# gps.net
KiCad netlist of a schematic drawn in EAGLE
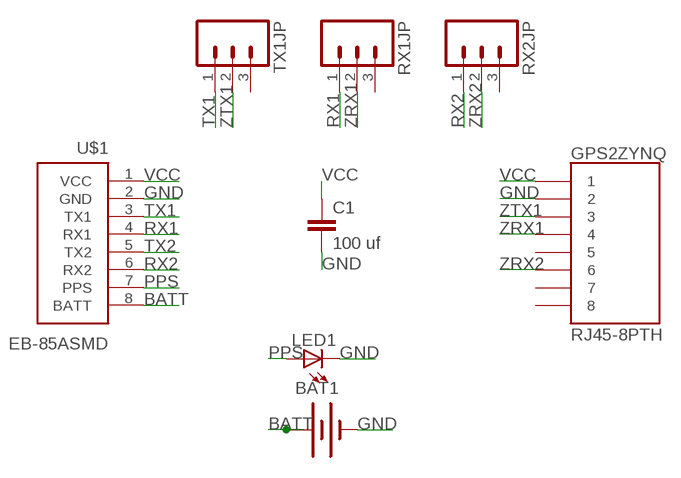
[diagram p0: schematic, sheet 1]

(export (version "E")
  (design (tool "Eeschema 10.0.6"))
  (components
    (comp (ref "BAT1")
      (value "BATTERY12PTH")
      (footprint "eagle-import:BATTCON_12MM_PTH")
      (libsource (lib "eagle-import") (part "BATTERY12PTH"))
    )
    (comp (ref "C1")
      (value "100 uf")
      (footprint "eagle-import:CAP-PTH-5MM")
      (libsource (lib "eagle-import") (part "CAPPTH1"))
    )
    (comp (ref "GPS2ZYNQ")
      (value "RJ45-8PTH")
      (footprint "eagle-import:RJ45-8")
      (libsource (lib "eagle-import") (part "RJ45-8PTH"))
    )
    (comp (ref "LED1")
      (value "LED5MM")
      (footprint "eagle-import:LED5MM")
      (libsource (lib "eagle-import") (part "LED5MM"))
    )
    (comp (ref "RX1JP")
      (value "M03LONGPADS")
      (footprint "eagle-import:1X03_LONGPADS")
      (libsource (lib "eagle-import") (part "M03LONGPADS"))
    )
    (comp (ref "RX2JP")
      (value "M03LONGPADS")
      (footprint "eagle-import:1X03_LONGPADS")
      (libsource (lib "eagle-import") (part "M03LONGPADS"))
    )
    (comp (ref "TX1JP")
      (value "M03LONGPADS")
      (footprint "eagle-import:1X03_LONGPADS")
      (libsource (lib "eagle-import") (part "M03LONGPADS"))
    )
    (comp (ref "U$1")
      (value "EB-85ASMD")
      (footprint "eagle-import:EB-85A")
      (libsource (lib "eagle-import") (part "EB-85ASMD"))
    )
  )
  (nets
    (net (code "1") (name "/BATT") (class "Default")
      (node (ref "BAT1") (pin "VCC@1") (pinfunction "+_VCC@1") (pintype "power_in"))
      (node (ref "U$1") (pin "8") (pinfunction "BATT_8") (pintype "power_in"))
    )
    (net (code "2") (name "/GND") (class "Default")
      (node (ref "BAT1") (pin "GND") (pinfunction "-_GND") (pintype "power_in"))
      (node (ref "C1") (pin "2") (pinfunction "2_2") (pintype "passive"))
      (node (ref "GPS2ZYNQ") (pin "2") (pinfunction "2_2") (pintype "bidirectional"))
      (node (ref "LED1") (pin "K") (pinfunction "C_K") (pintype "passive"))
      (node (ref "U$1") (pin "2") (pinfunction "GND_2") (pintype "power_in"))
    )
    (net (code "3") (name "/PPS") (class "Default")
      (node (ref "LED1") (pin "A") (pinfunction "A_A") (pintype "passive"))
      (node (ref "U$1") (pin "7") (pinfunction "PPS_7") (pintype "output"))
    )
    (net (code "4") (name "/RX1") (class "Default")
      (node (ref "RX1JP") (pin "1") (pinfunction "1_1") (pintype "passive"))
      (node (ref "U$1") (pin "4") (pinfunction "RX1_4") (pintype "input"))
    )
    (net (code "5") (name "/RX2") (class "Default")
      (node (ref "RX2JP") (pin "1") (pinfunction "1_1") (pintype "passive"))
      (node (ref "U$1") (pin "6") (pinfunction "RX2_6") (pintype "input"))
    )
    (net (code "6") (name "/TX1") (class "Default")
      (node (ref "TX1JP") (pin "1") (pinfunction "1_1") (pintype "passive"))
      (node (ref "U$1") (pin "3") (pinfunction "TX1_3") (pintype "output"))
    )
    (net (code "7") (name "/TX2") (class "Default")
      (node (ref "U$1") (pin "5") (pinfunction "TX2_5") (pintype "output"))
    )
    (net (code "8") (name "/VCC") (class "Default")
      (node (ref "C1") (pin "1") (pinfunction "1_1") (pintype "passive"))
      (node (ref "GPS2ZYNQ") (pin "1") (pinfunction "1_1") (pintype "bidirectional"))
      (node (ref "U$1") (pin "1") (pinfunction "VCC_1") (pintype "power_in"))
    )
    (net (code "9") (name "/ZRX1") (class "Default")
      (node (ref "GPS2ZYNQ") (pin "4") (pinfunction "4_4") (pintype "bidirectional"))
      (node (ref "RX1JP") (pin "2") (pinfunction "2_2") (pintype "passive"))
    )
    (net (code "10") (name "/ZRX2") (class "Default")
      (node (ref "GPS2ZYNQ") (pin "6") (pinfunction "6_6") (pintype "bidirectional"))
      (node (ref "RX2JP") (pin "2") (pinfunction "2_2") (pintype "passive"))
    )
    (net (code "11") (name "/ZTX1") (class "Default")
      (node (ref "GPS2ZYNQ") (pin "3") (pinfunction "3_3") (pintype "bidirectional"))
      (node (ref "TX1JP") (pin "2") (pinfunction "2_2") (pintype "passive"))
    )
    (net (code "12") (name "unconnected-(GPS2ZYNQ-Pad5)") (class "Default")
      (node (ref "GPS2ZYNQ") (pin "5") (pinfunction "5_5") (pintype "bidirectional"))
    )
    (net (code "13") (name "unconnected-(GPS2ZYNQ-Pad7)") (class "Default")
      (node (ref "GPS2ZYNQ") (pin "7") (pinfunction "7_7") (pintype "bidirectional"))
    )
    (net (code "14") (name "unconnected-(GPS2ZYNQ-Pad8)") (class "Default")
      (node (ref "GPS2ZYNQ") (pin "8") (pinfunction "8_8") (pintype "bidirectional"))
    )
    (net (code "15") (name "unconnected-(RX1JP-Pad3)") (class "Default")
      (node (ref "RX1JP") (pin "3") (pinfunction "3_3") (pintype "passive"))
    )
    (net (code "16") (name "unconnected-(RX2JP-Pad3)") (class "Default")
      (node (ref "RX2JP") (pin "3") (pinfunction "3_3") (pintype "passive"))
    )
    (net (code "17") (name "unconnected-(TX1JP-Pad3)") (class "Default")
      (node (ref "TX1JP") (pin "3") (pinfunction "3_3") (pintype "passive"))
    )
  )
)
